# InkTime_Schematic.net
KiCad netlist of a schematic drawn in EAGLE
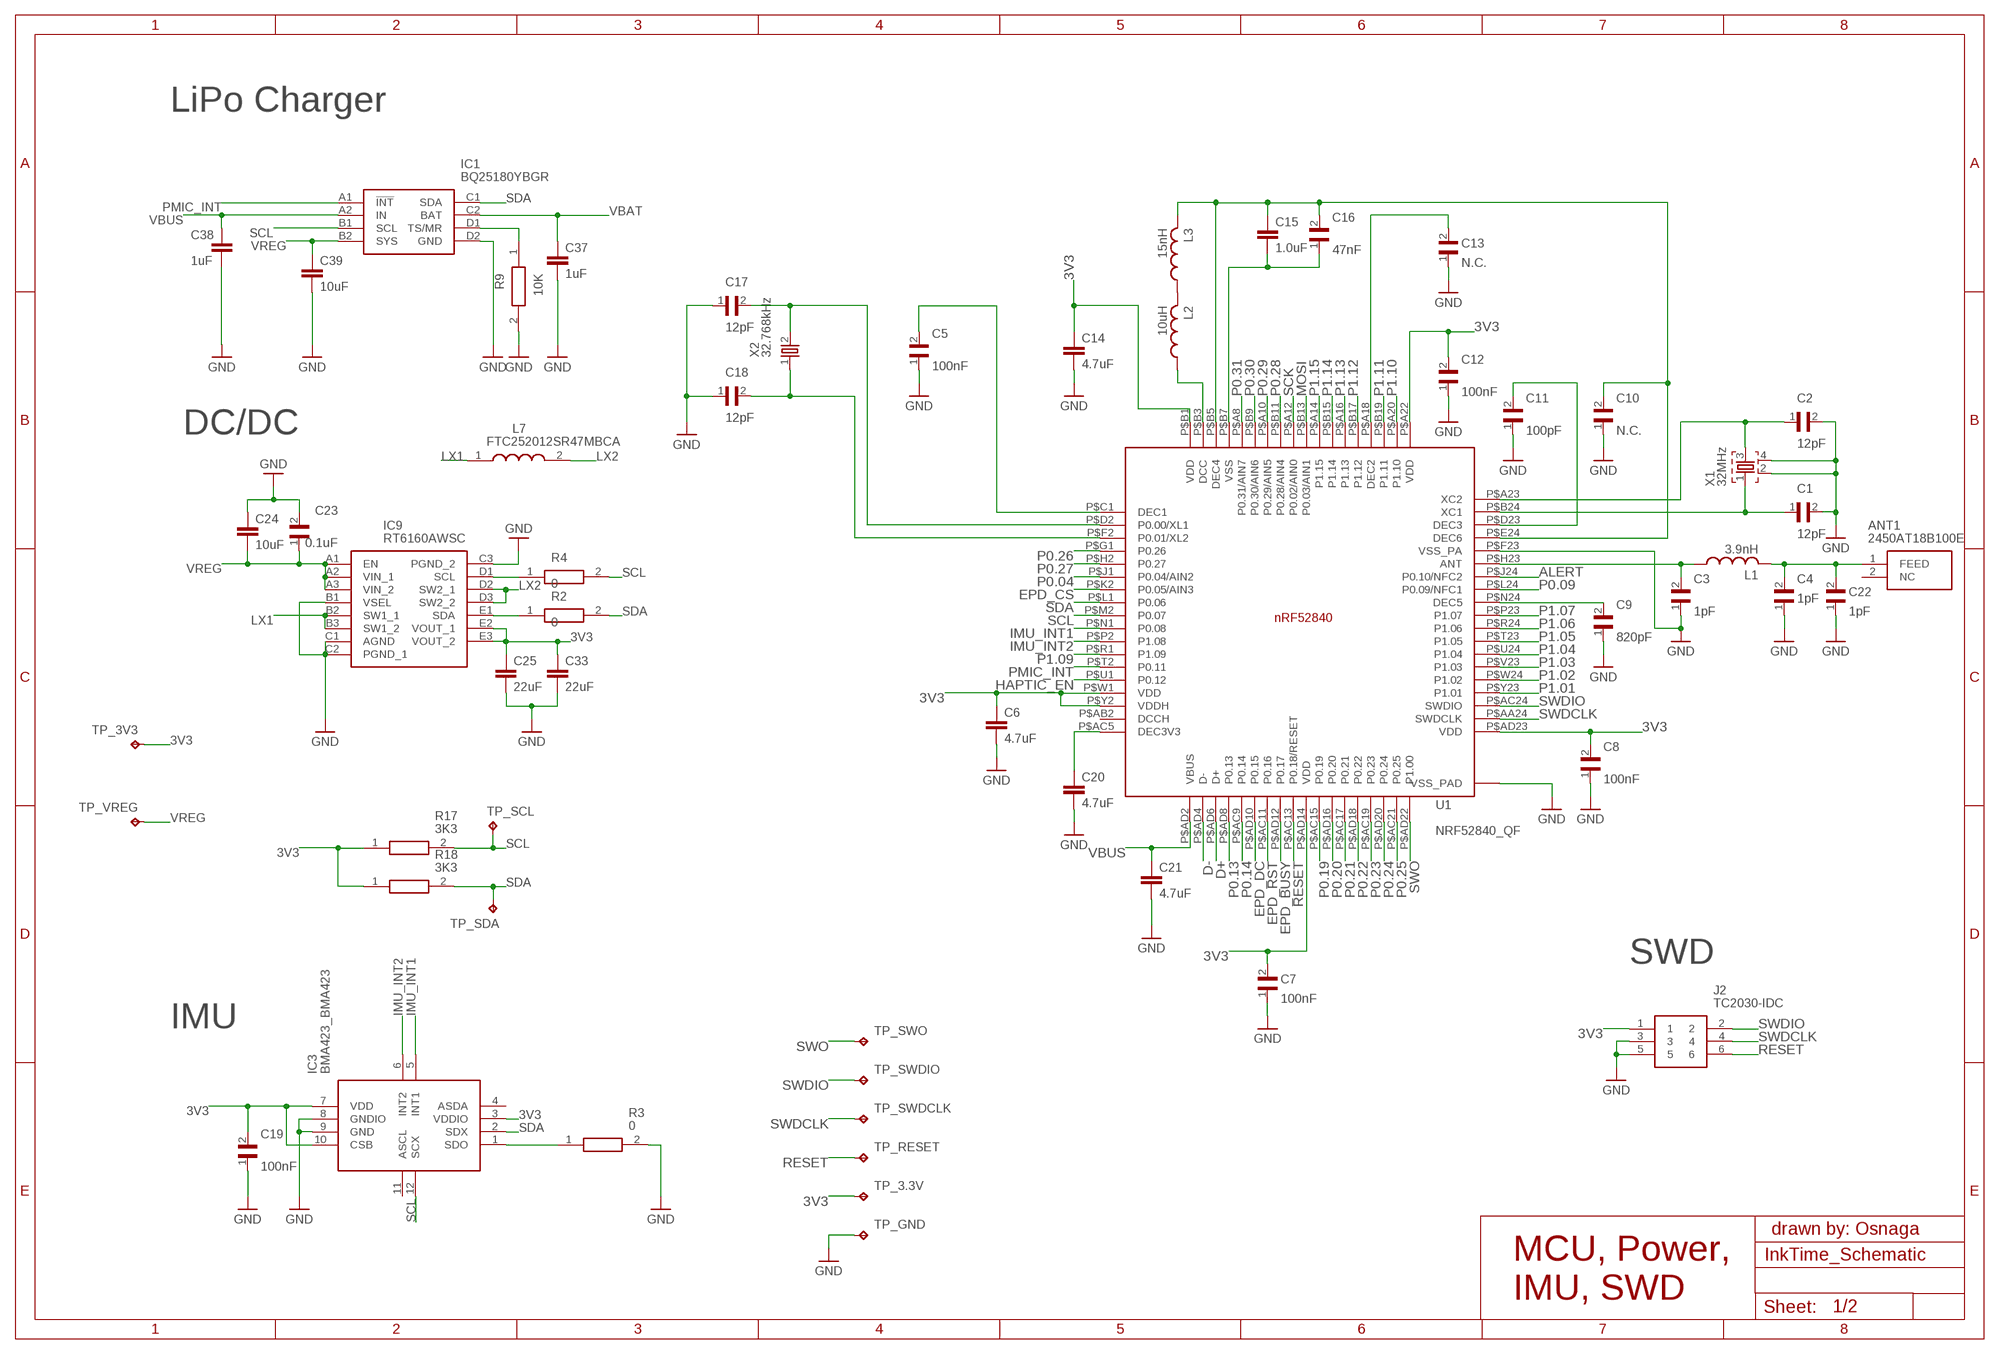
[diagram p0: schematic, sheet 1]
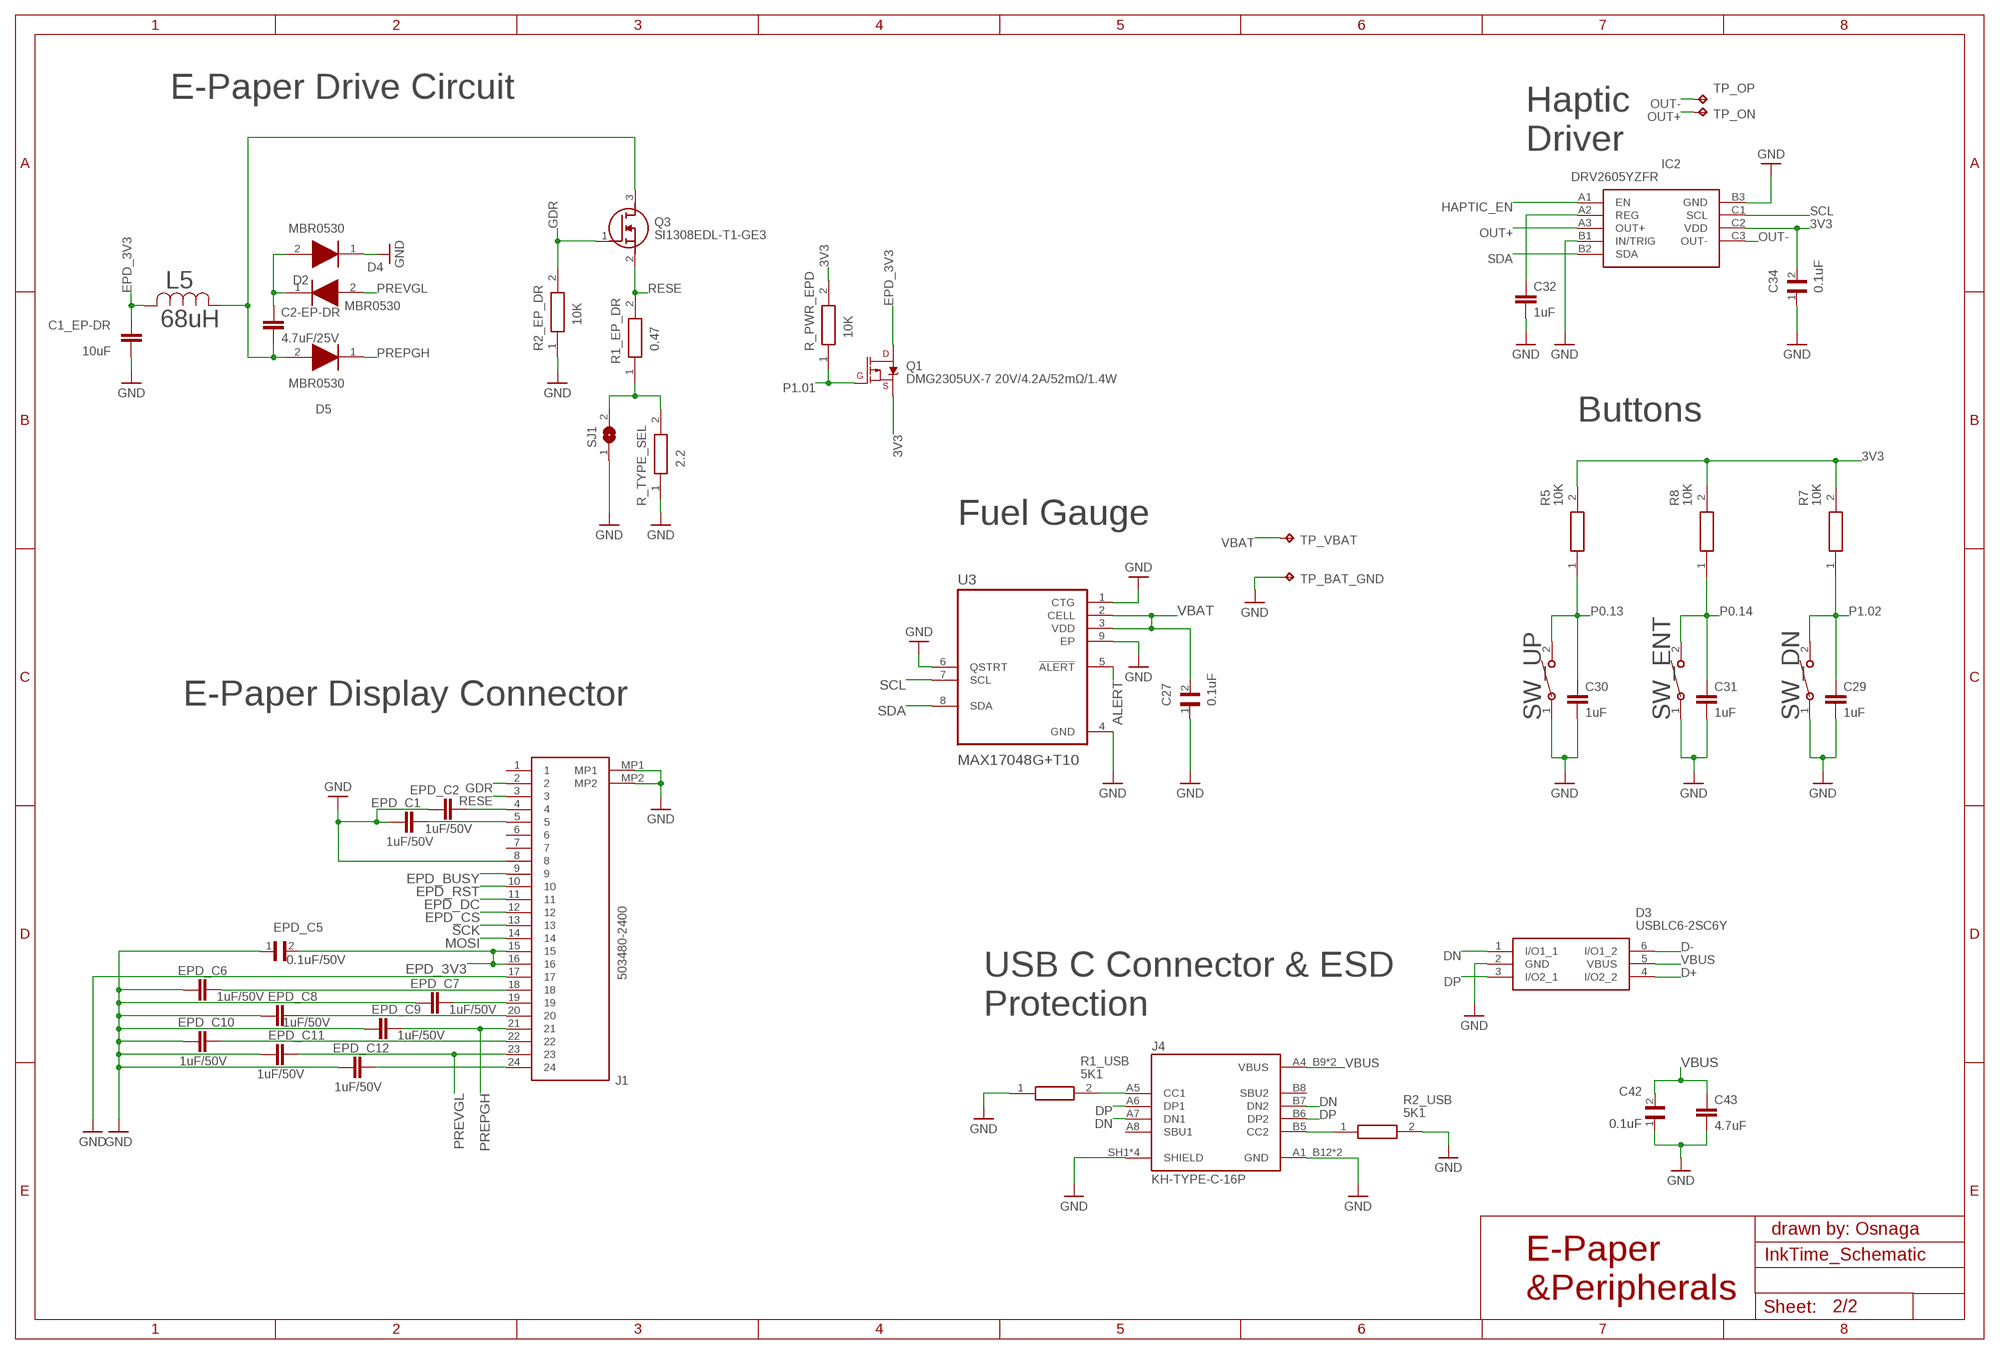
[diagram p1: schematic, sheet 2]

(export (version "E")
  (design (tool "Eeschema 10.0.6"))
  (components
    (comp (ref "C1_EP-DR")
      (value "10uF")
      (footprint "eagle-import:PERFECT_0402_0402")
      (libsource (lib "eagle-import") (part "PERFECT_0402_CAP_0402"))
    )
    (comp (ref "C2-EP-DR")
      (value "4.7uF/25V")
      (footprint "eagle-import:PERFECT_0402_0402")
      (libsource (lib "eagle-import") (part "PERFECT_0402_CAP_0402"))
    )
    (comp (ref "C27")
      (value "0.1uF")
      (footprint "eagle-import:GRM011R60J152KE01L_2_CAPC0201X13N")
      (fields (field (name "MF") "Murata") (field (name "MP") "GRM011R60J152KE01L"))
      (libsource (lib "eagle-import") (part "GRM011R60J152KE01L_2_GRM011R60J152KE01L"))
    )
    (comp (ref "C29")
      (value "1uF")
      (footprint "eagle-import:PERFECT_0402_0402")
      (libsource (lib "eagle-import") (part "PERFECT_0402_CAP_0402"))
    )
    (comp (ref "C30")
      (value "1uF")
      (footprint "eagle-import:PERFECT_0402_0402")
      (libsource (lib "eagle-import") (part "PERFECT_0402_CAP_0402"))
    )
    (comp (ref "C31")
      (value "1uF")
      (footprint "eagle-import:PERFECT_0402_0402")
      (libsource (lib "eagle-import") (part "PERFECT_0402_CAP_0402"))
    )
    (comp (ref "C32")
      (value "1uF")
      (footprint "eagle-import:PERFECT_0402_0402")
      (libsource (lib "eagle-import") (part "PERFECT_0402_CAP_0402"))
    )
    (comp (ref "C34")
      (value "0.1uF")
      (footprint "eagle-import:GRM011R60J152KE01L_2_CAPC0201X13N")
      (fields (field (name "MF") "Murata") (field (name "MP") "GRM011R60J152KE01L"))
      (libsource (lib "eagle-import") (part "GRM011R60J152KE01L_2_GRM011R60J152KE01L"))
    )
    (comp (ref "C42")
      (value "0.1uF")
      (footprint "eagle-import:GRM011R60J152KE01L_2_CAPC0201X13N")
      (fields (field (name "MF") "Murata") (field (name "MP") "GRM011R60J152KE01L"))
      (libsource (lib "eagle-import") (part "GRM011R60J152KE01L_2_GRM011R60J152KE01L"))
    )
    (comp (ref "C43")
      (value "4.7uF")
      (footprint "eagle-import:PERFECT_0402_0402")
      (libsource (lib "eagle-import") (part "PERFECT_0402_CAP_0402"))
    )
    (comp (ref "D2")
      (value "MBR0530")
      (footprint "eagle-import:ESP32_C6_LIBRARY_5_SOD3716X135N")
      (fields (field (name "MF") "ON Semiconductor"))
      (libsource (lib "eagle-import") (part "ESP32_C6_LIBRARY_5_MBR0530"))
    )
    (comp (ref "D3")
      (value "USBLC6-2SC6Y")
      (footprint "eagle-import:ESP32_C6_LIBRARY_3_SOT95P280X145-6N")
      (fields (field (name "MF") "STMicroelectronics"))
      (libsource (lib "eagle-import") (part "ESP32_C6_LIBRARY_3_USBLC6-2SC6Y"))
    )
    (comp (ref "D4")
      (value "MBR0530")
      (footprint "eagle-import:ESP32_C6_LIBRARY_5_SOD3716X135N")
      (fields (field (name "MF") "ON Semiconductor"))
      (libsource (lib "eagle-import") (part "ESP32_C6_LIBRARY_5_MBR0530"))
    )
    (comp (ref "D5")
      (value "MBR0530")
      (footprint "eagle-import:ESP32_C6_LIBRARY_5_SOD3716X135N")
      (fields (field (name "MF") "ON Semiconductor"))
      (libsource (lib "eagle-import") (part "ESP32_C6_LIBRARY_5_MBR0530"))
    )
    (comp (ref "EPD_C1")
      (value "1uF/50V")
      (footprint "eagle-import:PERFECT_0402_0402")
      (libsource (lib "eagle-import") (part "PERFECT_0402_CAP_0402"))
    )
    (comp (ref "EPD_C2")
      (value "1uF/50V")
      (footprint "eagle-import:PERFECT_0402_0402")
      (libsource (lib "eagle-import") (part "PERFECT_0402_CAP_0402"))
    )
    (comp (ref "EPD_C5")
      (value "0.1uF/50V")
      (footprint "eagle-import:GRM011R60J152KE01L_2_CAPC0201X13N")
      (fields (field (name "MF") "Murata") (field (name "MP") "GRM011R60J152KE01L"))
      (libsource (lib "eagle-import") (part "GRM011R60J152KE01L_2_GRM011R60J152KE01L"))
    )
    (comp (ref "EPD_C6")
      (value "1uF/50V")
      (footprint "eagle-import:PERFECT_0402_0402")
      (libsource (lib "eagle-import") (part "PERFECT_0402_CAP_0402"))
    )
    (comp (ref "EPD_C7")
      (value "1uF/50V")
      (footprint "eagle-import:PERFECT_0402_0402")
      (libsource (lib "eagle-import") (part "PERFECT_0402_CAP_0402"))
    )
    (comp (ref "EPD_C8")
      (value "1uF/50V")
      (footprint "eagle-import:PERFECT_0402_0402")
      (libsource (lib "eagle-import") (part "PERFECT_0402_CAP_0402"))
    )
    (comp (ref "EPD_C9")
      (value "1uF/50V")
      (footprint "eagle-import:PERFECT_0402_0402")
      (libsource (lib "eagle-import") (part "PERFECT_0402_CAP_0402"))
    )
    (comp (ref "EPD_C10")
      (value "1uF/50V")
      (footprint "eagle-import:PERFECT_0402_0402")
      (libsource (lib "eagle-import") (part "PERFECT_0402_CAP_0402"))
    )
    (comp (ref "EPD_C11")
      (value "1uF/50V")
      (footprint "eagle-import:PERFECT_0402_0402")
      (libsource (lib "eagle-import") (part "PERFECT_0402_CAP_0402"))
    )
    (comp (ref "EPD_C12")
      (value "1uF/50V")
      (footprint "eagle-import:PERFECT_0402_0402")
      (libsource (lib "eagle-import") (part "PERFECT_0402_CAP_0402"))
    )
    (comp (ref "IC2")
      (value "DRV2605YZFR")
      (footprint "eagle-import:DRV2605YZFR_BGA9C50P3X3_144X144X62")
      (libsource (lib "eagle-import") (part "DRV2605YZFR_DRV2605YZFR"))
    )
    (comp (ref "J1")
      (value "503480-2400")
      (footprint "eagle-import:503480-2400_5034802400")
      (fields (field (name "MOUSER_PART_NUMBER") "538-503480-2400"))
      (libsource (lib "eagle-import") (part "503480-2400_503480-2400"))
    )
    (comp (ref "J4")
      (value "KH-TYPE-C-16P")
      (footprint "eagle-import:KH-TYPE-C-16P_KINGHELM_KH-TYPE-C-16P")
      (fields (field (name "MF") "kinghelm"))
      (libsource (lib "eagle-import") (part "KH-TYPE-C-16P_KH-TYPE-C-16P"))
    )
    (comp (ref "L5")
      (value "68uH")
      (footprint "eagle-import:ESP32_C6_LIBRARY_2_IND_4828-WE-TPC_WRE")
      (fields
        (field (name "MANUFACTURER_PART_NUMBER") "744043680")
        (field (name "COPYRIGHT") "Copyright (C) 2024 Ultra Librarian. All rights reserved.")
      )
      (libsource (lib "eagle-import") (part "ESP32_C6_LIBRARY_2_744043680IND_4828-WE-TPC_WRE"))
    )
    (comp (ref "Q1")
      (value "DMG2305UX-7 20V/4.2A/52mΩ/1.4W")
      (footprint "eagle-import:ESP32_C6_LIBRARY_4_ESP32_C6_LIBRARY_4_ESP32_C6_LIBRARY_4_ESP32_C6_LIBRARY_4_ESP32_WROVER_SPARKFUN-DISCRETESEMI_SOT23-3")
      (libsource (lib "eagle-import") (part "ESP32_C6_LIBRARY_4_ESP32_WROVER_SPARKFUN-DISCRETESEMI_MOSFET_PCH-DMG2305UX-7"))
    )
    (comp (ref "Q3")
      (value "SI1308EDL-T1-GE3")
      (footprint "eagle-import:ESP32_C6_LIBRARY_6_SOT65P210X110-3N")
      (fields (field (name "MF") "Vishay Siliconix"))
      (libsource (lib "eagle-import") (part "ESP32_C6_LIBRARY_6_SI1308EDL-T1-GE3"))
    )
    (comp (ref "R1_EP_DR")
      (value "0.47")
      (footprint "eagle-import:CPF0201D7K68C1_0201")
      (libsource (lib "eagle-import") (part "CPF0201D7K68C1_CPF0201D7K68C1"))
    )
    (comp (ref "R1_USB")
      (value "5K1")
      (footprint "eagle-import:CPF0201D7K68C1_0201")
      (libsource (lib "eagle-import") (part "CPF0201D7K68C1_CPF0201D7K68C1"))
    )
    (comp (ref "R2_EP_DR")
      (value "10K")
      (footprint "eagle-import:CPF0201D7K68C1_0201")
      (libsource (lib "eagle-import") (part "CPF0201D7K68C1_CPF0201D7K68C1"))
    )
    (comp (ref "R2_USB")
      (value "5K1")
      (footprint "eagle-import:CPF0201D7K68C1_0201")
      (libsource (lib "eagle-import") (part "CPF0201D7K68C1_CPF0201D7K68C1"))
    )
    (comp (ref "R5")
      (value "10K")
      (footprint "eagle-import:CPF0201D7K68C1_0201")
      (libsource (lib "eagle-import") (part "CPF0201D7K68C1_CPF0201D7K68C1"))
    )
    (comp (ref "R7")
      (value "10K")
      (footprint "eagle-import:CPF0201D7K68C1_0201")
      (libsource (lib "eagle-import") (part "CPF0201D7K68C1_CPF0201D7K68C1"))
    )
    (comp (ref "R8")
      (value "10K")
      (footprint "eagle-import:CPF0201D7K68C1_0201")
      (libsource (lib "eagle-import") (part "CPF0201D7K68C1_CPF0201D7K68C1"))
    )
    (comp (ref "R_PWR_EPD")
      (value "10K")
      (footprint "eagle-import:CPF0201D7K68C1_0201")
      (libsource (lib "eagle-import") (part "CPF0201D7K68C1_CPF0201D7K68C1"))
    )
    (comp (ref "R_TYPE_SEL")
      (value "2.2")
      (footprint "eagle-import:CPF0201D7K68C1_0201")
      (libsource (lib "eagle-import") (part "CPF0201D7K68C1_CPF0201D7K68C1"))
    )
    (comp (ref "SJ1")
      (value "ESP32_C6_LIBRARY_7_JUMPER_SJ")
      (footprint "eagle-import:ESP32_C6_LIBRARY_7_JUMPER_SJ")
      (libsource (lib "eagle-import") (part "ESP32_C6_LIBRARY_7_JUMPER_SJ"))
    )
    (comp (ref "SW_DN")
      (value "2025-10-22_07-23-44_LIBRARY_EVP-AKE31ASW_EVP-AKE31A_PAN")
      (footprint "eagle-import:2025-10-22_07-23-44_LIBRARY_SW_EVP-AKE31A_PAN")
      (fields
        (field (name "MANUFACTURER_PART_NUMBER") "EVP-AKE31A")
        (field (name "COPYRIGHT") "Copyright (C) 2025 Ultra Librarian. All rights reserved.")
      )
      (libsource (lib "eagle-import") (part "2025-10-22_07-23-44_LIBRARY_EVP-AKE31ASW_EVP-AKE31A_PAN"))
    )
    (comp (ref "SW_ENT")
      (value "2025-10-22_07-23-44_LIBRARY_EVP-AKE31ASW_EVP-AKE31A_PAN")
      (footprint "eagle-import:2025-10-22_07-23-44_LIBRARY_SW_EVP-AKE31A_PAN")
      (fields
        (field (name "MANUFACTURER_PART_NUMBER") "EVP-AKE31A")
        (field (name "COPYRIGHT") "Copyright (C) 2025 Ultra Librarian. All rights reserved.")
      )
      (libsource (lib "eagle-import") (part "2025-10-22_07-23-44_LIBRARY_EVP-AKE31ASW_EVP-AKE31A_PAN"))
    )
    (comp (ref "SW_UP")
      (value "2025-10-22_07-23-44_LIBRARY_EVP-AKE31ASW_EVP-AKE31A_PAN")
      (footprint "eagle-import:2025-10-22_07-23-44_LIBRARY_SW_EVP-AKE31A_PAN")
      (fields
        (field (name "MANUFACTURER_PART_NUMBER") "EVP-AKE31A")
        (field (name "COPYRIGHT") "Copyright (C) 2025 Ultra Librarian. All rights reserved.")
      )
      (libsource (lib "eagle-import") (part "2025-10-22_07-23-44_LIBRARY_EVP-AKE31ASW_EVP-AKE31A_PAN"))
    )
    (comp (ref "TP_BAT_GND")
      (value "HECTOR_WATCH_1_TPTP20R")
      (footprint "eagle-import:HECTOR_WATCH_1_TP20R")
      (libsource (lib "eagle-import") (part "HECTOR_WATCH_1_TPTP20R"))
    )
    (comp (ref "TP_ON")
      (value "HECTOR_WATCH_1_TPTP20R")
      (footprint "eagle-import:HECTOR_WATCH_1_TP20R")
      (libsource (lib "eagle-import") (part "HECTOR_WATCH_1_TPTP20R"))
    )
    (comp (ref "TP_OP")
      (value "HECTOR_WATCH_1_TPTP20R")
      (footprint "eagle-import:HECTOR_WATCH_1_TP20R")
      (libsource (lib "eagle-import") (part "HECTOR_WATCH_1_TPTP20R"))
    )
    (comp (ref "TP_VBAT")
      (value "HECTOR_WATCH_1_TPTP20R")
      (footprint "eagle-import:HECTOR_WATCH_1_TP20R")
      (libsource (lib "eagle-import") (part "HECTOR_WATCH_1_TPTP20R"))
    )
    (comp (ref "U3")
      (value "MAX17048G+T10")
      (footprint "eagle-import:ESP32_C6_LIBRARY_SON50P200X200X80-9N")
      (fields (field (name "MF") "Analog Devices"))
      (libsource (lib "eagle-import") (part "ESP32_C6_LIBRARY_MAX17048G+T10"))
    )
    (comp (ref "ANT1")
      (value "2450AT18B100E")
      (footprint "eagle-import:2450AT18B100E_ANTC3216X140N")
      (fields (field (name "MOUSER_PART_NUMBER") "609-2450AT18B100E"))
      (libsource (lib "eagle-import") (part "2450AT18B100E_2450AT18B100E"))
    )
    (comp (ref "C1")
      (value "12pF")
      (footprint "eagle-import:GRM011R60J152KE01L_2_CAPC0201X13N")
      (fields (field (name "MF") "Murata") (field (name "MP") "GRM011R60J152KE01L"))
      (libsource (lib "eagle-import") (part "GRM011R60J152KE01L_2_GRM011R60J152KE01L"))
    )
    (comp (ref "C2")
      (value "12pF")
      (footprint "eagle-import:GRM011R60J152KE01L_2_CAPC0201X13N")
      (fields (field (name "MF") "Murata") (field (name "MP") "GRM011R60J152KE01L"))
      (libsource (lib "eagle-import") (part "GRM011R60J152KE01L_2_GRM011R60J152KE01L"))
    )
    (comp (ref "C3")
      (value "1pF")
      (footprint "eagle-import:GRM011R60J152KE01L_2_CAPC0201X13N")
      (fields (field (name "MF") "Murata") (field (name "MP") "GRM011R60J152KE01L"))
      (libsource (lib "eagle-import") (part "GRM011R60J152KE01L_2_GRM011R60J152KE01L"))
    )
    (comp (ref "C4")
      (value "1pF")
      (footprint "eagle-import:GRM011R60J152KE01L_2_CAPC0201X13N")
      (fields (field (name "MF") "Murata") (field (name "MP") "GRM011R60J152KE01L"))
      (libsource (lib "eagle-import") (part "GRM011R60J152KE01L_2_GRM011R60J152KE01L"))
    )
    (comp (ref "C5")
      (value "100nF")
      (footprint "eagle-import:GRM011R60J152KE01L_2_CAPC0201X13N")
      (fields (field (name "MF") "Murata") (field (name "MP") "GRM011R60J152KE01L"))
      (libsource (lib "eagle-import") (part "GRM011R60J152KE01L_2_GRM011R60J152KE01L"))
    )
    (comp (ref "C6")
      (value "4.7uF")
      (footprint "eagle-import:PERFECT_0402_0402")
      (libsource (lib "eagle-import") (part "PERFECT_0402_CAP_0402"))
    )
    (comp (ref "C7")
      (value "100nF")
      (footprint "eagle-import:GRM011R60J152KE01L_2_CAPC0201X13N")
      (fields (field (name "MF") "Murata") (field (name "MP") "GRM011R60J152KE01L"))
      (libsource (lib "eagle-import") (part "GRM011R60J152KE01L_2_GRM011R60J152KE01L"))
    )
    (comp (ref "C8")
      (value "100nF")
      (footprint "eagle-import:GRM011R60J152KE01L_2_CAPC0201X13N")
      (fields (field (name "MF") "Murata") (field (name "MP") "GRM011R60J152KE01L"))
      (libsource (lib "eagle-import") (part "GRM011R60J152KE01L_2_GRM011R60J152KE01L"))
    )
    (comp (ref "C9")
      (value "820pF")
      (footprint "eagle-import:GRM011R60J152KE01L_2_CAPC0201X13N")
      (fields (field (name "MF") "Murata") (field (name "MP") "GRM011R60J152KE01L"))
      (libsource (lib "eagle-import") (part "GRM011R60J152KE01L_2_GRM011R60J152KE01L"))
    )
    (comp (ref "C10")
      (value "N.C.")
      (footprint "eagle-import:GRM011R60J152KE01L_2_CAPC0201X13N")
      (fields (field (name "MF") "Murata") (field (name "MP") "GRM011R60J152KE01L"))
      (libsource (lib "eagle-import") (part "GRM011R60J152KE01L_2_GRM011R60J152KE01L"))
    )
    (comp (ref "C11")
      (value "100pF")
      (footprint "eagle-import:GRM011R60J152KE01L_2_CAPC0201X13N")
      (fields (field (name "MF") "Murata") (field (name "MP") "GRM011R60J152KE01L"))
      (libsource (lib "eagle-import") (part "GRM011R60J152KE01L_2_GRM011R60J152KE01L"))
    )
    (comp (ref "C12")
      (value "100nF")
      (footprint "eagle-import:GRM011R60J152KE01L_2_CAPC0201X13N")
      (fields (field (name "MF") "Murata") (field (name "MP") "GRM011R60J152KE01L"))
      (libsource (lib "eagle-import") (part "GRM011R60J152KE01L_2_GRM011R60J152KE01L"))
    )
    (comp (ref "C13")
      (value "N.C.")
      (footprint "eagle-import:GRM011R60J152KE01L_2_CAPC0201X13N")
      (fields (field (name "MF") "Murata") (field (name "MP") "GRM011R60J152KE01L"))
      (libsource (lib "eagle-import") (part "GRM011R60J152KE01L_2_GRM011R60J152KE01L"))
    )
    (comp (ref "C14")
      (value "4.7uF")
      (footprint "eagle-import:PERFECT_0402_0402")
      (libsource (lib "eagle-import") (part "PERFECT_0402_CAP_0402"))
    )
    (comp (ref "C15")
      (value "1.0uF")
      (footprint "eagle-import:PERFECT_0402_0402")
      (libsource (lib "eagle-import") (part "PERFECT_0402_CAP_0402"))
    )
    (comp (ref "C16")
      (value "47nF")
      (footprint "eagle-import:GRM011R60J152KE01L_2_CAPC0201X13N")
      (fields (field (name "MF") "Murata") (field (name "MP") "GRM011R60J152KE01L"))
      (libsource (lib "eagle-import") (part "GRM011R60J152KE01L_2_GRM011R60J152KE01L"))
    )
    (comp (ref "C17")
      (value "12pF")
      (footprint "eagle-import:GRM011R60J152KE01L_2_CAPC0201X13N")
      (fields (field (name "MF") "Murata") (field (name "MP") "GRM011R60J152KE01L"))
      (libsource (lib "eagle-import") (part "GRM011R60J152KE01L_2_GRM011R60J152KE01L"))
    )
    (comp (ref "C18")
      (value "12pF")
      (footprint "eagle-import:GRM011R60J152KE01L_2_CAPC0201X13N")
      (fields (field (name "MF") "Murata") (field (name "MP") "GRM011R60J152KE01L"))
      (libsource (lib "eagle-import") (part "GRM011R60J152KE01L_2_GRM011R60J152KE01L"))
    )
    (comp (ref "C19")
      (value "100nF")
      (footprint "eagle-import:GRM011R60J152KE01L_2_CAPC0201X13N")
      (fields (field (name "MF") "Murata") (field (name "MP") "GRM011R60J152KE01L"))
      (libsource (lib "eagle-import") (part "GRM011R60J152KE01L_2_GRM011R60J152KE01L"))
    )
    (comp (ref "C20")
      (value "4.7uF")
      (footprint "eagle-import:PERFECT_0402_0402")
      (libsource (lib "eagle-import") (part "PERFECT_0402_CAP_0402"))
    )
    (comp (ref "C21")
      (value "4.7uF")
      (footprint "eagle-import:PERFECT_0402_0402")
      (libsource (lib "eagle-import") (part "PERFECT_0402_CAP_0402"))
    )
    (comp (ref "C22")
      (value "1pF")
      (footprint "eagle-import:GRM011R60J152KE01L_2_CAPC0201X13N")
      (fields (field (name "MF") "Murata") (field (name "MP") "GRM011R60J152KE01L"))
      (libsource (lib "eagle-import") (part "GRM011R60J152KE01L_2_GRM011R60J152KE01L"))
    )
    (comp (ref "C23")
      (value "0.1uF")
      (footprint "eagle-import:GRM011R60J152KE01L_2_CAPC0201X13N")
      (fields (field (name "MF") "Murata") (field (name "MP") "GRM011R60J152KE01L"))
      (libsource (lib "eagle-import") (part "GRM011R60J152KE01L_2_GRM011R60J152KE01L"))
    )
    (comp (ref "C24")
      (value "10uF")
      (footprint "eagle-import:PERFECT_0402_0402")
      (libsource (lib "eagle-import") (part "PERFECT_0402_CAP_0402"))
    )
    (comp (ref "C25")
      (value "22uF")
      (footprint "eagle-import:PERFECT_0402_0402")
      (libsource (lib "eagle-import") (part "PERFECT_0402_CAP_0402"))
    )
    (comp (ref "C33")
      (value "22uF")
      (footprint "eagle-import:PERFECT_0402_0402")
      (libsource (lib "eagle-import") (part "PERFECT_0402_CAP_0402"))
    )
    (comp (ref "C37")
      (value "1uF")
      (footprint "eagle-import:PERFECT_0402_0402")
      (libsource (lib "eagle-import") (part "PERFECT_0402_CAP_0402"))
    )
    (comp (ref "C38")
      (value "1uF")
      (footprint "eagle-import:PERFECT_0402_0402")
      (libsource (lib "eagle-import") (part "PERFECT_0402_CAP_0402"))
    )
    (comp (ref "C39")
      (value "10uF")
      (footprint "eagle-import:PERFECT_0402_0402")
      (libsource (lib "eagle-import") (part "PERFECT_0402_CAP_0402"))
    )
    (comp (ref "IC1")
      (value "BQ25180YBGR")
      (footprint "eagle-import:BQ25180YBGR_BGA8C40P2X4_100X155X50")
      (fields (field (name "MOUSER_PART_NUMBER") "595-BQ25180YBGR"))
      (libsource (lib "eagle-import") (part "BQ25180YBGR_BQ25180YBGR"))
    )
    (comp (ref "IC3")
      (value "BMA423_BMA423")
      (footprint "eagle-import:BMA423_BMA423")
      (fields (field (name "ARROW_PART_NUMBER") "BMA423") (field (name "MOUSER_PART_NUMBER") "262-BMA423"))
      (libsource (lib "eagle-import") (part "BMA423_BMA423"))
    )
    (comp (ref "IC9")
      (value "RT6160AWSC")
      (footprint "eagle-import:RT6160AWSC_BGA15C40P3X5_140X230X60")
      (fields (field (name "MOUSER_PART_NUMBER") "835-RT6160AWSC"))
      (libsource (lib "eagle-import") (part "RT6160AWSC_RT6160AWSC"))
    )
    (comp (ref "J2")
      (value "TC2030-IDC")
      (footprint "eagle-import:TC2030-IDC_TC2030IDC")
      (libsource (lib "eagle-import") (part "TC2030-IDC_TC2030-IDC"))
    )
    (comp (ref "L1")
      (value "3.9nH")
      (footprint "eagle-import:NORDIC_NRF_2_RESC0201_L")
      (libsource (lib "eagle-import") (part "NORDIC_NRF_2_INDUCTOR_0201_L"))
    )
    (comp (ref "L2")
      (value "10uH")
      (footprint "eagle-import:NORDIC_NRF_2_RESC0201_L")
      (libsource (lib "eagle-import") (part "NORDIC_NRF_2_INDUCTOR_0201_L"))
    )
    (comp (ref "L3")
      (value "15nH")
      (footprint "eagle-import:NORDIC_NRF_2_RESC0201_L")
      (libsource (lib "eagle-import") (part "NORDIC_NRF_2_INDUCTOR_0201_L"))
    )
    (comp (ref "L7")
      (value "FTC252012SR47MBCA")
      (footprint "eagle-import:MLP2016SR47MT0S1_INDC2016X100N")
      (libsource (lib "eagle-import") (part "MLP2016SR47MT0S1_FTC252012SR47MBCA"))
    )
    (comp (ref "R2")
      (value "0")
      (footprint "eagle-import:CPF0201D7K68C1_0201")
      (libsource (lib "eagle-import") (part "CPF0201D7K68C1_CPF0201D7K68C1"))
    )
    (comp (ref "R3")
      (value "0")
      (footprint "eagle-import:CPF0201D7K68C1_0201")
      (libsource (lib "eagle-import") (part "CPF0201D7K68C1_CPF0201D7K68C1"))
    )
    (comp (ref "R4")
      (value "0")
      (footprint "eagle-import:CPF0201D7K68C1_0201")
      (libsource (lib "eagle-import") (part "CPF0201D7K68C1_CPF0201D7K68C1"))
    )
    (comp (ref "R9")
      (value "10K")
      (footprint "eagle-import:CPF0201D7K68C1_0201")
      (libsource (lib "eagle-import") (part "CPF0201D7K68C1_CPF0201D7K68C1"))
    )
    (comp (ref "R17")
      (value "3K3")
      (footprint "eagle-import:CPF0201D7K68C1_0201")
      (libsource (lib "eagle-import") (part "CPF0201D7K68C1_CPF0201D7K68C1"))
    )
    (comp (ref "R18")
      (value "3K3")
      (footprint "eagle-import:CPF0201D7K68C1_0201")
      (libsource (lib "eagle-import") (part "CPF0201D7K68C1_CPF0201D7K68C1"))
    )
    (comp (ref "TP_3.3V")
      (value "HECTOR_WATCH_1_TPTP20R")
      (footprint "eagle-import:HECTOR_WATCH_1_TP20R")
      (libsource (lib "eagle-import") (part "HECTOR_WATCH_1_TPTP20R"))
    )
    (comp (ref "TP_3V3")
      (value "HECTOR_WATCH_1_TPTP20R")
      (footprint "eagle-import:HECTOR_WATCH_1_TP20R")
      (libsource (lib "eagle-import") (part "HECTOR_WATCH_1_TPTP20R"))
    )
    (comp (ref "TP_GND")
      (value "HECTOR_WATCH_1_TPTP20R")
      (footprint "eagle-import:HECTOR_WATCH_1_TP20R")
      (libsource (lib "eagle-import") (part "HECTOR_WATCH_1_TPTP20R"))
    )
    (comp (ref "TP_RESET")
      (value "HECTOR_WATCH_1_TPTP20R")
      (footprint "eagle-import:HECTOR_WATCH_1_TP20R")
      (libsource (lib "eagle-import") (part "HECTOR_WATCH_1_TPTP20R"))
    )
    (comp (ref "TP_SCL")
      (value "HECTOR_WATCH_1_TPTP20R")
      (footprint "eagle-import:HECTOR_WATCH_1_TP20R")
      (libsource (lib "eagle-import") (part "HECTOR_WATCH_1_TPTP20R"))
    )
    (comp (ref "TP_SDA")
      (value "HECTOR_WATCH_1_TPTP20R")
      (footprint "eagle-import:HECTOR_WATCH_1_TP20R")
      (libsource (lib "eagle-import") (part "HECTOR_WATCH_1_TPTP20R"))
    )
    (comp (ref "TP_SWDCLK")
      (value "HECTOR_WATCH_1_TPTP20R")
      (footprint "eagle-import:HECTOR_WATCH_1_TP20R")
      (libsource (lib "eagle-import") (part "HECTOR_WATCH_1_TPTP20R"))
    )
    (comp (ref "TP_SWDIO")
      (value "HECTOR_WATCH_1_TPTP20R")
      (footprint "eagle-import:HECTOR_WATCH_1_TP20R")
      (libsource (lib "eagle-import") (part "HECTOR_WATCH_1_TPTP20R"))
    )
    (comp (ref "TP_SWO")
      (value "HECTOR_WATCH_1_TPTP20R")
      (footprint "eagle-import:HECTOR_WATCH_1_TP20R")
      (libsource (lib "eagle-import") (part "HECTOR_WATCH_1_TPTP20R"))
    )
    (comp (ref "TP_VREG")
      (value "HECTOR_WATCH_1_TPTP20R")
      (footprint "eagle-import:HECTOR_WATCH_1_TP20R")
      (libsource (lib "eagle-import") (part "HECTOR_WATCH_1_TPTP20R"))
    )
    (comp (ref "U1")
      (value "NRF52840_QF")
      (footprint "eagle-import:NORDIC_NRF_4_AQFN50P700X700X85_HS-74N")
      (libsource (lib "eagle-import") (part "NORDIC_NRF_4_NRF52840_QF"))
    )
    (comp (ref "X1")
      (value "32MHz")
      (footprint "eagle-import:NORDIC_NRF_BT-XTAL_2016_N")
      (libsource (lib "eagle-import") (part "NORDIC_NRF_XTAL_32MHZ"))
    )
    (comp (ref "X2")
      (value "32.768kHz")
      (footprint "eagle-import:NORDIC_NRF_1_XTAL_3215_N")
      (libsource (lib "eagle-import") (part "NORDIC_NRF_1_XTAL_32KHZ"))
    )
  )
  (nets
    (net (code "1") (name "3V3") (class "Default")
      (node (ref "C12") (pin "2") (pinfunction "2_2") (pintype "passive"))
      (node (ref "C14") (pin "1") (pinfunction "1_1") (pintype "passive"))
      (node (ref "C19") (pin "2") (pinfunction "2_2") (pintype "passive"))
      (node (ref "C25") (pin "1") (pinfunction "1_1") (pintype "passive"))
      (node (ref "C33") (pin "1") (pinfunction "1_1") (pintype "passive"))
      (node (ref "C34") (pin "2") (pinfunction "2_2") (pintype "passive"))
      (node (ref "C6") (pin "1") (pinfunction "1_1") (pintype "passive"))
      (node (ref "C7") (pin "2") (pinfunction "2_2") (pintype "passive"))
      (node (ref "C8") (pin "2") (pinfunction "2_2") (pintype "passive"))
      (node (ref "IC2") (pin "C2") (pinfunction "VDD_C2") (pintype "bidirectional"))
      (node (ref "IC3") (pin "10") (pinfunction "CSB_10") (pintype "bidirectional"))
      (node (ref "IC3") (pin "3") (pinfunction "VDDIO_3") (pintype "bidirectional"))
      (node (ref "IC3") (pin "7") (pinfunction "VDD_7") (pintype "bidirectional"))
      (node (ref "IC9") (pin "E2") (pinfunction "VOUT_1_E2") (pintype "bidirectional"))
      (node (ref "IC9") (pin "E3") (pinfunction "VOUT_2_E3") (pintype "bidirectional"))
      (node (ref "J2") (pin "1") (pinfunction "1_1") (pintype "bidirectional"))
      (node (ref "Q1") (pin "2") (pinfunction "S_2") (pintype "bidirectional"))
      (node (ref "R17") (pin "1") (pinfunction "1_1") (pintype "bidirectional"))
      (node (ref "R18") (pin "1") (pinfunction "1_1") (pintype "bidirectional"))
      (node (ref "R5") (pin "2") (pinfunction "2_2") (pintype "bidirectional"))
      (node (ref "R7") (pin "2") (pinfunction "2_2") (pintype "bidirectional"))
      (node (ref "R8") (pin "2") (pinfunction "2_2") (pintype "bidirectional"))
      (node (ref "R_PWR_EPD") (pin "2") (pinfunction "2_2") (pintype "bidirectional"))
      (node (ref "TP_3.3V") (pin "TP") (pinfunction "TP_TP") (pintype "input"))
      (node (ref "TP_3V3") (pin "TP") (pinfunction "TP_TP") (pintype "input"))
      (node (ref "U1") (pin "P$A22") (pinfunction "VDD_P$A22") (pintype "power_in"))
      (node (ref "U1") (pin "P$AD14") (pinfunction "VDD_P$AD14") (pintype "power_in"))
      (node (ref "U1") (pin "P$AD23") (pinfunction "VDD_P$AD23") (pintype "power_in"))
      (node (ref "U1") (pin "P$B1") (pinfunction "VDD_P$B1") (pintype "power_in"))
      (node (ref "U1") (pin "P$W1") (pinfunction "VDD_P$W1") (pintype "power_in"))
      (node (ref "U1") (pin "P$Y2") (pinfunction "VDDH_P$Y2") (pintype "power_in"))
    )
    (net (code "2") (name "ALERT") (class "Default")
      (node (ref "U1") (pin "P$J24") (pinfunction "P0.10/NFC2_P$J24") (pintype "bidirectional"))
      (node (ref "U3") (pin "5") (pinfunction "~{ALERT}_5") (pintype "output"))
    )
    (net (code "3") (name "D+") (class "Default")
      (node (ref "D3") (pin "4") (pinfunction "I/O2_2_4") (pintype "bidirectional"))
      (node (ref "U1") (pin "P$AD6") (pinfunction "D+_P$AD6") (pintype "bidirectional"))
    )
    (net (code "4") (name "D-") (class "Default")
      (node (ref "D3") (pin "6") (pinfunction "I/O1_2_6") (pintype "bidirectional"))
      (node (ref "U1") (pin "P$AD4") (pinfunction "D-_P$AD4") (pintype "bidirectional"))
    )
    (net (code "5") (name "DN") (class "Default")
      (node (ref "D3") (pin "1") (pinfunction "I/O1_1_1") (pintype "bidirectional"))
      (node (ref "J4") (pin "A7") (pinfunction "DN1_A7") (pintype "bidirectional"))
      (node (ref "J4") (pin "B7") (pinfunction "DN2_B7") (pintype "bidirectional"))
    )
    (net (code "6") (name "DP") (class "Default")
      (node (ref "D3") (pin "3") (pinfunction "I/O2_1_3") (pintype "bidirectional"))
      (node (ref "J4") (pin "A6") (pinfunction "DP1_A6") (pintype "bidirectional"))
      (node (ref "J4") (pin "B6") (pinfunction "DP2_B6") (pintype "bidirectional"))
    )
    (net (code "7") (name "EPD_3V3") (class "Default")
      (node (ref "C1_EP-DR") (pin "1") (pinfunction "1_1") (pintype "passive"))
      (node (ref "EPD_C5") (pin "2") (pinfunction "2_2") (pintype "passive"))
      (node (ref "J1") (pin "15") (pinfunction "15_15") (pintype "bidirectional"))
      (node (ref "J1") (pin "16") (pinfunction "16_16") (pintype "bidirectional"))
      (node (ref "L5") (pin "2") (pinfunction "2_2") (pintype "passive"))
      (node (ref "Q1") (pin "3") (pinfunction "D_3") (pintype "bidirectional"))
    )
    (net (code "8") (name "EPD_BUSY") (class "Default")
      (node (ref "J1") (pin "9") (pinfunction "9_9") (pintype "bidirectional"))
      (node (ref "U1") (pin "P$AD12") (pinfunction "P0.17_P$AD12") (pintype "bidirectional"))
    )
    (net (code "9") (name "EPD_CS") (class "Default")
      (node (ref "J1") (pin "12") (pinfunction "12_12") (pintype "bidirectional"))
      (node (ref "U1") (pin "P$K2") (pinfunction "P0.05/AIN3_P$K2") (pintype "bidirectional"))
    )
    (net (code "10") (name "EPD_DC") (class "Default")
      (node (ref "J1") (pin "11") (pinfunction "11_11") (pintype "bidirectional"))
      (node (ref "U1") (pin "P$AD10") (pinfunction "P0.15_P$AD10") (pintype "bidirectional"))
    )
    (net (code "11") (name "EPD_RST") (class "Default")
      (node (ref "J1") (pin "10") (pinfunction "10_10") (pintype "bidirectional"))
      (node (ref "U1") (pin "P$AC11") (pinfunction "P0.16_P$AC11") (pintype "bidirectional"))
    )
    (net (code "12") (name "GDR") (class "Default")
      (node (ref "J1") (pin "2") (pinfunction "2_2") (pintype "bidirectional"))
      (node (ref "Q3") (pin "1") (pinfunction "G_1") (pintype "bidirectional"))
      (node (ref "R2_EP_DR") (pin "2") (pinfunction "2_2") (pintype "bidirectional"))
    )
    (net (code "13") (name "GND") (class "Default")
      (node (ref "C1") (pin "2") (pinfunction "2_2") (pintype "passive"))
      (node (ref "C10") (pin "1") (pinfunction "1_1") (pintype "passive"))
      (node (ref "C11") (pin "1") (pinfunction "1_1") (pintype "passive"))
      (node (ref "C12") (pin "1") (pinfunction "1_1") (pintype "passive"))
      (node (ref "C13") (pin "1") (pinfunction "1_1") (pintype "passive"))
      (node (ref "C14") (pin "2") (pinfunction "2_2") (pintype "passive"))
      (node (ref "C17") (pin "1") (pinfunction "1_1") (pintype "passive"))
      (node (ref "C18") (pin "1") (pinfunction "1_1") (pintype "passive"))
      (node (ref "C19") (pin "1") (pinfunction "1_1") (pintype "passive"))
      (node (ref "C1_EP-DR") (pin "2") (pinfunction "2_2") (pintype "passive"))
      (node (ref "C2") (pin "2") (pinfunction "2_2") (pintype "passive"))
      (node (ref "C20") (pin "2") (pinfunction "2_2") (pintype "passive"))
      (node (ref "C21") (pin "2") (pinfunction "2_2") (pintype "passive"))
      (node (ref "C22") (pin "1") (pinfunction "1_1") (pintype "passive"))
      (node (ref "C23") (pin "2") (pinfunction "2_2") (pintype "passive"))
      (node (ref "C24") (pin "1") (pinfunction "1_1") (pintype "passive"))
      (node (ref "C25") (pin "2") (pinfunction "2_2") (pintype "passive"))
      (node (ref "C27") (pin "1") (pinfunction "1_1") (pintype "passive"))
      (node (ref "C29") (pin "2") (pinfunction "2_2") (pintype "passive"))
      (node (ref "C3") (pin "1") (pinfunction "1_1") (pintype "passive"))
      (node (ref "C30") (pin "2") (pinfunction "2_2") (pintype "passive"))
      (node (ref "C31") (pin "2") (pinfunction "2_2") (pintype "passive"))
      (node (ref "C32") (pin "2") (pinfunction "2_2") (pintype "passive"))
      (node (ref "C33") (pin "2") (pinfunction "2_2") (pintype "passive"))
      (node (ref "C34") (pin "1") (pinfunction "1_1") (pintype "passive"))
      (node (ref "C37") (pin "2") (pinfunction "2_2") (pintype "passive"))
      (node (ref "C38") (pin "2") (pinfunction "2_2") (pintype "passive"))
      (node (ref "C39") (pin "2") (pinfunction "2_2") (pintype "passive"))
      (node (ref "C4") (pin "1") (pinfunction "1_1") (pintype "passive"))
      (node (ref "C42") (pin "1") (pinfunction "1_1") (pintype "passive"))
      (node (ref "C43") (pin "2") (pinfunction "2_2") (pintype "passive"))
      (node (ref "C5") (pin "1") (pinfunction "1_1") (pintype "passive"))
      (node (ref "C6") (pin "2") (pinfunction "2_2") (pintype "passive"))
      (node (ref "C7") (pin "1") (pinfunction "1_1") (pintype "passive"))
      (node (ref "C8") (pin "1") (pinfunction "1_1") (pintype "passive"))
      (node (ref "C9") (pin "1") (pinfunction "1_1") (pintype "passive"))
      (node (ref "D3") (pin "2") (pinfunction "GND_2") (pintype "bidirectional"))
      (node (ref "D4") (pin "1") (pinfunction "K_1") (pintype "bidirectional"))
      (node (ref "EPD_C1") (pin "1") (pinfunction "1_1") (pintype "passive"))
      (node (ref "EPD_C10") (pin "1") (pinfunction "1_1") (pintype "passive"))
      (node (ref "EPD_C11") (pin "1") (pinfunction "1_1") (pintype "passive"))
      (node (ref "EPD_C12") (pin "1") (pinfunction "1_1") (pintype "passive"))
      (node (ref "EPD_C2") (pin "1") (pinfunction "1_1") (pintype "passive"))
      (node (ref "EPD_C5") (pin "1") (pinfunction "1_1") (pintype "passive"))
      (node (ref "EPD_C6") (pin "1") (pinfunction "1_1") (pintype "passive"))
      (node (ref "EPD_C7") (pin "1") (pinfunction "1_1") (pintype "passive"))
      (node (ref "EPD_C8") (pin "1") (pinfunction "1_1") (pintype "passive"))
      (node (ref "EPD_C9") (pin "1") (pinfunction "1_1") (pintype "passive"))
      (node (ref "IC1") (pin "D2") (pinfunction "GND_D2") (pintype "bidirectional"))
      (node (ref "IC2") (pin "B1") (pinfunction "IN/TRIG_B1") (pintype "bidirectional"))
      (node (ref "IC2") (pin "B3") (pinfunction "GND_B3") (pintype "bidirectional"))
      (node (ref "IC3") (pin "8") (pinfunction "GNDIO_8") (pintype "bidirectional"))
      (node (ref "IC3") (pin "9") (pinfunction "GND_9") (pintype "bidirectional"))
      (node (ref "IC9") (pin "B1") (pinfunction "VSEL_B1") (pintype "bidirectional"))
      (node (ref "IC9") (pin "C1") (pinfunction "AGND_C1") (pintype "bidirectional"))
      (node (ref "IC9") (pin "C2") (pinfunction "PGND_1_C2") (pintype "bidirectional"))
      (node (ref "IC9") (pin "C3") (pinfunction "PGND_2_C3") (pintype "bidirectional"))
      (node (ref "J1") (pin "17") (pinfunction "17_17") (pintype "bidirectional"))
      (node (ref "J1") (pin "8") (pinfunction "8_8") (pintype "bidirectional"))
      (node (ref "J1") (pin "MP1") (pinfunction "MP1_MP1") (pintype "bidirectional"))
      (node (ref "J1") (pin "MP2") (pinfunction "MP2_MP2") (pintype "bidirectional"))
      (node (ref "J2") (pin "3") (pinfunction "3_3") (pintype "bidirectional"))
      (node (ref "J2") (pin "5") (pinfunction "5_5") (pintype "bidirectional"))
      (node (ref "J4") (pin "A12_B1") (pinfunction "GND_A12_B1") (pintype "power_in"))
      (node (ref "J4") (pin "A1_B12") (pinfunction "GND_A1_B12") (pintype "power_in"))
      (node (ref "J4") (pin "SH1") (pinfunction "SHIELD_SH1") (pintype "passive"))
      (node (ref "J4") (pin "SH2") (pinfunction "SHIELD_SH2") (pintype "passive"))
      (node (ref "J4") (pin "SH3") (pinfunction "SHIELD_SH3") (pintype "passive"))
      (node (ref "J4") (pin "SH4") (pinfunction "SHIELD_SH4") (pintype "passive"))
      (node (ref "R1_USB") (pin "1") (pinfunction "1_1") (pintype "bidirectional"))
      (node (ref "R2_EP_DR") (pin "1") (pinfunction "1_1") (pintype "bidirectional"))
      (node (ref "R2_USB") (pin "2") (pinfunction "2_2") (pintype "bidirectional"))
      (node (ref "R3") (pin "2") (pinfunction "2_2") (pintype "bidirectional"))
      (node (ref "R9") (pin "2") (pinfunction "2_2") (pintype "bidirectional"))
      (node (ref "R_TYPE_SEL") (pin "1") (pinfunction "1_1") (pintype "bidirectional"))
      (node (ref "SJ1") (pin "1") (pinfunction "1_1") (pintype "passive"))
      (node (ref "SW_DN") (pin "1") (pinfunction "1_1") (pintype "passive"))
      (node (ref "SW_ENT") (pin "1") (pinfunction "1_1") (pintype "passive"))
      (node (ref "SW_UP") (pin "1") (pinfunction "1_1") (pintype "passive"))
      (node (ref "TP_BAT_GND") (pin "TP") (pinfunction "TP_TP") (pintype "input"))
      (node (ref "TP_GND") (pin "TP") (pinfunction "TP_TP") (pintype "input"))
      (node (ref "U1") (pin "P$74") (pinfunction "VSS_PAD_P$74") (pintype "bidirectional"))
      (node (ref "U1") (pin "P$75") (pinfunction "VSS_PAD_P$75") (pintype "bidirectional"))
      (node (ref "U1") (pin "P$76") (pinfunction "VSS_PAD_P$76") (pintype "bidirectional"))
      (node (ref "U1") (pin "P$77") (pinfunction "VSS_PAD_P$77") (pintype "bidirectional"))
      (node (ref "U1") (pin "P$78") (pinfunction "VSS_PAD_P$78") (pintype "bidirectional"))
      (node (ref "U1") (pin "P$79") (pinfunction "VSS_PAD_P$79") (pintype "bidirectional"))
      (node (ref "U1") (pin "P$80") (pinfunction "VSS_PAD_P$80") (pintype "bidirectional"))
      (node (ref "U1") (pin "P$81") (pinfunction "VSS_PAD_P$81") (pintype "bidirectional"))
      (node (ref "U1") (pin "P$82") (pinfunction "VSS_PAD_P$82") (pintype "bidirectional"))
      (node (ref "U1") (pin "P$83") (pinfunction "VSS_PAD_P$83") (pintype "bidirectional"))
      (node (ref "U1") (pin "P$84") (pinfunction "VSS_PAD_P$84") (pintype "bidirectional"))
      (node (ref "U1") (pin "P$85") (pinfunction "VSS_PAD_P$85") (pintype "bidirectional"))
      (node (ref "U1") (pin "P$86") (pinfunction "VSS_PAD_P$86") (pintype "bidirectional"))
      (node (ref "U1") (pin "P$87") (pinfunction "VSS_PAD_P$87") (pintype "bidirectional"))
      (node (ref "U1") (pin "P$88") (pinfunction "VSS_PAD_P$88") (pintype "bidirectional"))
      (node (ref "U1") (pin "P$89") (pinfunction "VSS_PAD_P$89") (pintype "bidirectional"))
      (node (ref "U1") (pin "P$90") (pinfunction "VSS_PAD_P$90") (pintype "bidirectional"))
      (node (ref "U1") (pin "P$F23") (pinfunction "VSS_PA_P$F23") (pintype "bidirectional"))
      (node (ref "U3") (pin "1") (pinfunction "CTG_1") (pintype "power_in"))
      (node (ref "U3") (pin "4") (pinfunction "GND_4") (pintype "power_in"))
      (node (ref "U3") (pin "6") (pinfunction "QSTRT_6") (pintype "input"))
      (node (ref "U3") (pin "9") (pinfunction "EP_9") (pintype "power_in"))
      (node (ref "X1") (pin "2") (pinfunction "2_2") (pintype "passive"))
      (node (ref "X1") (pin "4") (pinfunction "4_4") (pintype "passive"))
    )
    (net (code "14") (name "HAPTIC_EN") (class "Default")
      (node (ref "IC2") (pin "A1") (pinfunction "EN_A1") (pintype "bidirectional"))
      (node (ref "U1") (pin "P$U1") (pinfunction "P0.12_P$U1") (pintype "bidirectional"))
    )
    (net (code "15") (name "IMU_INT1") (class "Default")
      (node (ref "IC3") (pin "5") (pinfunction "INT1_5") (pintype "bidirectional"))
      (node (ref "U1") (pin "P$N1") (pinfunction "P0.08_P$N1") (pintype "bidirectional"))
    )
    (net (code "16") (name "IMU_INT2") (class "Default")
      (node (ref "IC3") (pin "6") (pinfunction "INT2_6") (pintype "bidirectional"))
      (node (ref "U1") (pin "P$P2") (pinfunction "P1.08_P$P2") (pintype "bidirectional"))
    )
    (net (code "17") (name "LX1") (class "Default")
      (node (ref "IC9") (pin "B2") (pinfunction "SW1_1_B2") (pintype "bidirectional"))
      (node (ref "IC9") (pin "B3") (pinfunction "SW1_2_B3") (pintype "bidirectional"))
      (node (ref "L7") (pin "1") (pinfunction "1_1") (pintype "bidirectional"))
    )
    (net (code "18") (name "LX2") (class "Default")
      (node (ref "IC9") (pin "D2") (pinfunction "SW2_1_D2") (pintype "bidirectional"))
      (node (ref "IC9") (pin "D3") (pinfunction "SW2_2_D3") (pintype "bidirectional"))
      (node (ref "L7") (pin "2") (pinfunction "2_2") (pintype "bidirectional"))
    )
    (net (code "19") (name "MOSI") (class "Default")
      (node (ref "J1") (pin "14") (pinfunction "14_14") (pintype "bidirectional"))
      (node (ref "U1") (pin "P$B13") (pinfunction "P0.03/AIN1_P$B13") (pintype "bidirectional"))
    )
    (net (code "20") (name "Net-(ANT1-FEED)") (class "Default")
      (node (ref "ANT1") (pin "1") (pinfunction "FEED_1") (pintype "input"))
      (node (ref "C22") (pin "2") (pinfunction "2_2") (pintype "passive"))
      (node (ref "C4") (pin "2") (pinfunction "2_2") (pintype "passive"))
      (node (ref "L1") (pin "2") (pinfunction "2_2") (pintype "passive"))
    )
    (net (code "21") (name "Net-(D2-K)") (class "Default")
      (node (ref "C2-EP-DR") (pin "1") (pinfunction "1_1") (pintype "passive"))
      (node (ref "D2") (pin "1") (pinfunction "K_1") (pintype "bidirectional"))
      (node (ref "D4") (pin "2") (pinfunction "A_2") (pintype "bidirectional"))
    )
    (net (code "22") (name "Net-(D5-A)") (class "Default")
      (node (ref "C2-EP-DR") (pin "2") (pinfunction "2_2") (pintype "passive"))
      (node (ref "D5") (pin "2") (pinfunction "A_2") (pintype "bidirectional"))
      (node (ref "L5") (pin "1") (pinfunction "1_1") (pintype "passive"))
      (node (ref "Q3") (pin "3") (pinfunction "D_3") (pintype "bidirectional"))
    )
    (net (code "23") (name "Net-(EPD_C1-Pad2)") (class "Default")
      (node (ref "EPD_C1") (pin "2") (pinfunction "2_2") (pintype "passive"))
      (node (ref "J1") (pin "5") (pinfunction "5_5") (pintype "bidirectional"))
    )
    (net (code "24") (name "Net-(EPD_C2-Pad2)") (class "Default")
      (node (ref "EPD_C2") (pin "2") (pinfunction "2_2") (pintype "passive"))
      (node (ref "J1") (pin "4") (pinfunction "4_4") (pintype "bidirectional"))
    )
    (net (code "25") (name "Net-(EPD_C6-Pad2)") (class "Default")
      (node (ref "EPD_C6") (pin "2") (pinfunction "2_2") (pintype "passive"))
      (node (ref "J1") (pin "18") (pinfunction "18_18") (pintype "bidirectional"))
    )
    (net (code "26") (name "Net-(EPD_C7-Pad2)") (class "Default")
      (node (ref "EPD_C7") (pin "2") (pinfunction "2_2") (pintype "passive"))
      (node (ref "J1") (pin "19") (pinfunction "19_19") (pintype "bidirectional"))
    )
    (net (code "27") (name "Net-(EPD_C8-Pad2)") (class "Default")
      (node (ref "EPD_C8") (pin "2") (pinfunction "2_2") (pintype "passive"))
      (node (ref "J1") (pin "20") (pinfunction "20_20") (pintype "bidirectional"))
    )
    (net (code "28") (name "Net-(EPD_C10-Pad2)") (class "Default")
      (node (ref "EPD_C10") (pin "2") (pinfunction "2_2") (pintype "passive"))
      (node (ref "J1") (pin "22") (pinfunction "22_22") (pintype "bidirectional"))
    )
    (net (code "29") (name "Net-(EPD_C12-Pad2)") (class "Default")
      (node (ref "EPD_C12") (pin "2") (pinfunction "2_2") (pintype "passive"))
      (node (ref "J1") (pin "24") (pinfunction "24_24") (pintype "bidirectional"))
    )
    (net (code "30") (name "Net-(IC1-TS{slash}MR)") (class "Default")
      (node (ref "IC1") (pin "D1") (pinfunction "TS/MR_D1") (pintype "bidirectional"))
      (node (ref "R9") (pin "1") (pinfunction "1_1") (pintype "bidirectional"))
    )
    (net (code "31") (name "Net-(IC2-REG)") (class "Default")
      (node (ref "C32") (pin "1") (pinfunction "1_1") (pintype "passive"))
      (node (ref "IC2") (pin "A2") (pinfunction "REG_A2") (pintype "bidirectional"))
    )
    (net (code "32") (name "Net-(IC3-SDO)") (class "Default")
      (node (ref "IC3") (pin "1") (pinfunction "SDO_1") (pintype "bidirectional"))
      (node (ref "R3") (pin "1") (pinfunction "1_1") (pintype "bidirectional"))
    )
    (net (code "33") (name "Net-(IC9-SCL)") (class "Default")
      (node (ref "IC9") (pin "D1") (pinfunction "SCL_D1") (pintype "bidirectional"))
      (node (ref "R4") (pin "1") (pinfunction "1_1") (pintype "bidirectional"))
    )
    (net (code "34") (name "Net-(IC9-SDA)") (class "Default")
      (node (ref "IC9") (pin "E1") (pinfunction "SDA_E1") (pintype "bidirectional"))
      (node (ref "R2") (pin "1") (pinfunction "1_1") (pintype "bidirectional"))
    )
    (net (code "35") (name "Net-(J4-CC1)") (class "Default")
      (node (ref "J4") (pin "A5") (pinfunction "CC1_A5") (pintype "bidirectional"))
      (node (ref "R1_USB") (pin "2") (pinfunction "2_2") (pintype "bidirectional"))
    )
    (net (code "36") (name "Net-(J4-CC2)") (class "Default")
      (node (ref "J4") (pin "B5") (pinfunction "CC2_B5") (pintype "bidirectional"))
      (node (ref "R2_USB") (pin "1") (pinfunction "1_1") (pintype "bidirectional"))
    )
    (net (code "37") (name "Net-(L2-Pad2)") (class "Default")
      (node (ref "L2") (pin "2") (pinfunction "2_2") (pintype "passive"))
      (node (ref "L3") (pin "1") (pinfunction "1_1") (pintype "passive"))
    )
    (net (code "38") (name "Net-(R1_EP_DR-Pad1)") (class "Default")
      (node (ref "R1_EP_DR") (pin "1") (pinfunction "1_1") (pintype "bidirectional"))
      (node (ref "R_TYPE_SEL") (pin "2") (pinfunction "2_2") (pintype "bidirectional"))
      (node (ref "SJ1") (pin "2") (pinfunction "2_2") (pintype "passive"))
    )
    (net (code "39") (name "Net-(U1-ANT)") (class "Default")
      (node (ref "C3") (pin "2") (pinfunction "2_2") (pintype "passive"))
      (node (ref "L1") (pin "1") (pinfunction "1_1") (pintype "passive"))
      (node (ref "U1") (pin "P$H23") (pinfunction "ANT_P$H23") (pintype "bidirectional"))
    )
    (net (code "40") (name "Net-(U1-DCC)") (class "Default")
      (node (ref "L2") (pin "1") (pinfunction "1_1") (pintype "passive"))
      (node (ref "U1") (pin "P$B3") (pinfunction "DCC_P$B3") (pintype "output"))
    )
    (net (code "41") (name "Net-(U1-DEC1)") (class "Default")
      (node (ref "C5") (pin "2") (pinfunction "2_2") (pintype "passive"))
      (node (ref "U1") (pin "P$C1") (pinfunction "DEC1_P$C1") (pintype "power_in"))
    )
    (net (code "42") (name "Net-(U1-DEC2)") (class "Default")
      (node (ref "C13") (pin "2") (pinfunction "2_2") (pintype "passive"))
      (node (ref "U1") (pin "P$A18") (pinfunction "DEC2_P$A18") (pintype "bidirectional"))
    )
    (net (code "43") (name "Net-(U1-DEC3)") (class "Default")
      (node (ref "C11") (pin "2") (pinfunction "2_2") (pintype "passive"))
      (node (ref "U1") (pin "P$D23") (pinfunction "DEC3_P$D23") (pintype "bidirectional"))
    )
    (net (code "44") (name "Net-(U1-DEC3V3)") (class "Default")
      (node (ref "C20") (pin "1") (pinfunction "1_1") (pintype "passive"))
      (node (ref "U1") (pin "P$AC5") (pinfunction "DEC3V3_P$AC5") (pintype "bidirectional"))
    )
    (net (code "45") (name "Net-(U1-DEC4)") (class "Default")
      (node (ref "C10") (pin "2") (pinfunction "2_2") (pintype "passive"))
      (node (ref "C15") (pin "1") (pinfunction "1_1") (pintype "passive"))
      (node (ref "C16") (pin "2") (pinfunction "2_2") (pintype "passive"))
      (node (ref "L3") (pin "2") (pinfunction "2_2") (pintype "passive"))
      (node (ref "U1") (pin "P$B5") (pinfunction "DEC4_P$B5") (pintype "power_in"))
      (node (ref "U1") (pin "P$E24") (pinfunction "DEC6_P$E24") (pintype "bidirectional"))
    )
    (net (code "46") (name "Net-(U1-DEC5)") (class "Default")
      (node (ref "C9") (pin "2") (pinfunction "2_2") (pintype "passive"))
      (node (ref "U1") (pin "P$N24") (pinfunction "DEC5_P$N24") (pintype "bidirectional"))
    )
    (net (code "47") (name "Net-(U1-P0.00{slash}XL1)") (class "Default")
      (node (ref "C17") (pin "2") (pinfunction "2_2") (pintype "passive"))
      (node (ref "U1") (pin "P$D2") (pinfunction "P0.00/XL1_P$D2") (pintype "bidirectional"))
      (node (ref "X2") (pin "2") (pinfunction "2_2") (pintype "passive"))
    )
    (net (code "48") (name "Net-(U1-P0.01{slash}XL2)") (class "Default")
      (node (ref "C18") (pin "2") (pinfunction "2_2") (pintype "passive"))
      (node (ref "U1") (pin "P$F2") (pinfunction "P0.01/XL2_P$F2") (pintype "bidirectional"))
      (node (ref "X2") (pin "1") (pinfunction "1_1") (pintype "passive"))
    )
    (net (code "49") (name "Net-(U1-VSS)") (class "Default")
      (node (ref "C15") (pin "2") (pinfunction "2_2") (pintype "passive"))
      (node (ref "C16") (pin "1") (pinfunction "1_1") (pintype "passive"))
      (node (ref "U1") (pin "P$B7") (pinfunction "VSS_P$B7") (pintype "power_in"))
    )
    (net (code "50") (name "Net-(U1-XC1)") (class "Default")
      (node (ref "C1") (pin "1") (pinfunction "1_1") (pintype "passive"))
      (node (ref "U1") (pin "P$B24") (pinfunction "XC1_P$B24") (pintype "input"))
      (node (ref "X1") (pin "1") (pinfunction "1_1") (pintype "passive"))
    )
    (net (code "51") (name "Net-(U1-XC2)") (class "Default")
      (node (ref "C2") (pin "1") (pinfunction "1_1") (pintype "passive"))
      (node (ref "U1") (pin "P$A23") (pinfunction "XC2_P$A23") (pintype "output"))
      (node (ref "X1") (pin "3") (pinfunction "3_3") (pintype "passive"))
    )
    (net (code "52") (name "OUT+") (class "Default")
      (node (ref "IC2") (pin "A3") (pinfunction "OUT+_A3") (pintype "bidirectional"))
      (node (ref "TP_ON") (pin "TP") (pinfunction "TP_TP") (pintype "input"))
    )
    (net (code "53") (name "OUT-") (class "Default")
      (node (ref "IC2") (pin "C3") (pinfunction "OUT-_C3") (pintype "bidirectional"))
      (node (ref "TP_OP") (pin "TP") (pinfunction "TP_TP") (pintype "input"))
    )
    (net (code "54") (name "P0.04") (class "Default")
      (node (ref "U1") (pin "P$J1") (pinfunction "P0.04/AIN2_P$J1") (pintype "bidirectional"))
    )
    (net (code "55") (name "P0.09") (class "Default")
      (node (ref "U1") (pin "P$L24") (pinfunction "P0.09/NFC1_P$L24") (pintype "bidirectional"))
    )
    (net (code "56") (name "P0.13") (class "Default")
      (node (ref "C30") (pin "1") (pinfunction "1_1") (pintype "passive"))
      (node (ref "R5") (pin "1") (pinfunction "1_1") (pintype "bidirectional"))
      (node (ref "SW_UP") (pin "2") (pinfunction "2_2") (pintype "passive"))
      (node (ref "U1") (pin "P$AD8") (pinfunction "P0.13_P$AD8") (pintype "bidirectional"))
    )
    (net (code "57") (name "P0.14") (class "Default")
      (node (ref "C31") (pin "1") (pinfunction "1_1") (pintype "passive"))
      (node (ref "R8") (pin "1") (pinfunction "1_1") (pintype "bidirectional"))
      (node (ref "SW_ENT") (pin "2") (pinfunction "2_2") (pintype "passive"))
      (node (ref "U1") (pin "P$AC9") (pinfunction "P0.14_P$AC9") (pintype "bidirectional"))
    )
    (net (code "58") (name "P0.19") (class "Default")
      (node (ref "U1") (pin "P$AC15") (pinfunction "P0.19_P$AC15") (pintype "bidirectional"))
    )
    (net (code "59") (name "P0.20") (class "Default")
      (node (ref "U1") (pin "P$AD16") (pinfunction "P0.20_P$AD16") (pintype "bidirectional"))
    )
    (net (code "60") (name "P0.21") (class "Default")
      (node (ref "U1") (pin "P$AC17") (pinfunction "P0.21_P$AC17") (pintype "bidirectional"))
    )
    (net (code "61") (name "P0.22") (class "Default")
      (node (ref "U1") (pin "P$AD18") (pinfunction "P0.22_P$AD18") (pintype "bidirectional"))
    )
    (net (code "62") (name "P0.23") (class "Default")
      (node (ref "U1") (pin "P$AC19") (pinfunction "P0.23_P$AC19") (pintype "bidirectional"))
    )
    (net (code "63") (name "P0.24") (class "Default")
      (node (ref "U1") (pin "P$AD20") (pinfunction "P0.24_P$AD20") (pintype "bidirectional"))
    )
    (net (code "64") (name "P0.25") (class "Default")
      (node (ref "U1") (pin "P$AC21") (pinfunction "P0.25_P$AC21") (pintype "bidirectional"))
    )
    (net (code "65") (name "P0.26") (class "Default")
      (node (ref "U1") (pin "P$G1") (pinfunction "P0.26_P$G1") (pintype "bidirectional"))
    )
    (net (code "66") (name "P0.27") (class "Default")
      (node (ref "U1") (pin "P$H2") (pinfunction "P0.27_P$H2") (pintype "bidirectional"))
    )
    (net (code "67") (name "P0.28") (class "Default")
      (node (ref "U1") (pin "P$B11") (pinfunction "P0.28/AIN4_P$B11") (pintype "bidirectional"))
    )
    (net (code "68") (name "P0.29") (class "Default")
      (node (ref "U1") (pin "P$A10") (pinfunction "P0.29/AIN5_P$A10") (pintype "bidirectional"))
    )
    (net (code "69") (name "P0.30") (class "Default")
      (node (ref "U1") (pin "P$B9") (pinfunction "P0.30/AIN6_P$B9") (pintype "bidirectional"))
    )
    (net (code "70") (name "P0.31") (class "Default")
      (node (ref "U1") (pin "P$A8") (pinfunction "P0.31/AIN7_P$A8") (pintype "bidirectional"))
    )
    (net (code "71") (name "P1.01") (class "Default")
      (node (ref "Q1") (pin "1") (pinfunction "G_1") (pintype "bidirectional"))
      (node (ref "R_PWR_EPD") (pin "1") (pinfunction "1_1") (pintype "bidirectional"))
      (node (ref "U1") (pin "P$Y23") (pinfunction "P1.01_P$Y23") (pintype "bidirectional"))
    )
    (net (code "72") (name "P1.02") (class "Default")
      (node (ref "C29") (pin "1") (pinfunction "1_1") (pintype "passive"))
      (node (ref "R7") (pin "1") (pinfunction "1_1") (pintype "bidirectional"))
      (node (ref "SW_DN") (pin "2") (pinfunction "2_2") (pintype "passive"))
      (node (ref "U1") (pin "P$W24") (pinfunction "P1.02_P$W24") (pintype "bidirectional"))
    )
    (net (code "73") (name "P1.03") (class "Default")
      (node (ref "U1") (pin "P$V23") (pinfunction "P1.03_P$V23") (pintype "bidirectional"))
    )
    (net (code "74") (name "P1.04") (class "Default")
      (node (ref "U1") (pin "P$U24") (pinfunction "P1.04_P$U24") (pintype "bidirectional"))
    )
    (net (code "75") (name "P1.05") (class "Default")
      (node (ref "U1") (pin "P$T23") (pinfunction "P1.05_P$T23") (pintype "bidirectional"))
    )
    (net (code "76") (name "P1.06") (class "Default")
      (node (ref "U1") (pin "P$R24") (pinfunction "P1.06_P$R24") (pintype "bidirectional"))
    )
    (net (code "77") (name "P1.07") (class "Default")
      (node (ref "U1") (pin "P$P23") (pinfunction "P1.07_P$P23") (pintype "bidirectional"))
    )
    (net (code "78") (name "P1.09") (class "Default")
      (node (ref "U1") (pin "P$R1") (pinfunction "P1.09_P$R1") (pintype "bidirectional"))
    )
    (net (code "79") (name "P1.10") (class "Default")
      (node (ref "U1") (pin "P$A20") (pinfunction "P1.10_P$A20") (pintype "bidirectional"))
    )
    (net (code "80") (name "P1.11") (class "Default")
      (node (ref "U1") (pin "P$B19") (pinfunction "P1.11_P$B19") (pintype "bidirectional"))
    )
    (net (code "81") (name "P1.12") (class "Default")
      (node (ref "U1") (pin "P$B17") (pinfunction "P1.12_P$B17") (pintype "bidirectional"))
    )
    (net (code "82") (name "P1.13") (class "Default")
      (node (ref "U1") (pin "P$A16") (pinfunction "P1.13_P$A16") (pintype "bidirectional"))
    )
    (net (code "83") (name "P1.14") (class "Default")
      (node (ref "U1") (pin "P$B15") (pinfunction "P1.14_P$B15") (pintype "bidirectional"))
    )
    (net (code "84") (name "P1.15") (class "Default")
      (node (ref "U1") (pin "P$A14") (pinfunction "P1.15_P$A14") (pintype "bidirectional"))
    )
    (net (code "85") (name "PMIC_INT") (class "Default")
      (node (ref "IC1") (pin "A1") (pinfunction "~{INT}_A1") (pintype "bidirectional"))
      (node (ref "U1") (pin "P$T2") (pinfunction "P0.11_P$T2") (pintype "bidirectional"))
    )
    (net (code "86") (name "PREPGH") (class "Default")
      (node (ref "D5") (pin "1") (pinfunction "K_1") (pintype "bidirectional"))
      (node (ref "EPD_C9") (pin "2") (pinfunction "2_2") (pintype "passive"))
      (node (ref "J1") (pin "21") (pinfunction "21_21") (pintype "bidirectional"))
    )
    (net (code "87") (name "PREVGL") (class "Default")
      (node (ref "D2") (pin "2") (pinfunction "A_2") (pintype "bidirectional"))
      (node (ref "EPD_C11") (pin "2") (pinfunction "2_2") (pintype "passive"))
      (node (ref "J1") (pin "23") (pinfunction "23_23") (pintype "bidirectional"))
    )
    (net (code "88") (name "RESE") (class "Default")
      (node (ref "J1") (pin "3") (pinfunction "3_3") (pintype "bidirectional"))
      (node (ref "Q3") (pin "2") (pinfunction "S_2") (pintype "bidirectional"))
      (node (ref "R1_EP_DR") (pin "2") (pinfunction "2_2") (pintype "bidirectional"))
    )
    (net (code "89") (name "RESET") (class "Default")
      (node (ref "J2") (pin "6") (pinfunction "6_6") (pintype "bidirectional"))
      (node (ref "TP_RESET") (pin "TP") (pinfunction "TP_TP") (pintype "input"))
      (node (ref "U1") (pin "P$AC13") (pinfunction "P0.18/RESET_P$AC13") (pintype "bidirectional"))
    )
    (net (code "90") (name "SCK") (class "Default")
      (node (ref "J1") (pin "13") (pinfunction "13_13") (pintype "bidirectional"))
      (node (ref "U1") (pin "P$A12") (pinfunction "P0.02/AIN0_P$A12") (pintype "bidirectional"))
    )
    (net (code "91") (name "SCL") (class "Default")
      (node (ref "IC1") (pin "B1") (pinfunction "SCL_B1") (pintype "bidirectional"))
      (node (ref "IC2") (pin "C1") (pinfunction "SCL_C1") (pintype "bidirectional"))
      (node (ref "IC3") (pin "12") (pinfunction "SCX_12") (pintype "bidirectional"))
      (node (ref "R17") (pin "2") (pinfunction "2_2") (pintype "bidirectional"))
      (node (ref "R4") (pin "2") (pinfunction "2_2") (pintype "bidirectional"))
      (node (ref "TP_SCL") (pin "TP") (pinfunction "TP_TP") (pintype "input"))
      (node (ref "U1") (pin "P$M2") (pinfunction "P0.07_P$M2") (pintype "bidirectional"))
      (node (ref "U3") (pin "7") (pinfunction "SCL_7") (pintype "input"))
    )
    (net (code "92") (name "SDA") (class "Default")
      (node (ref "IC1") (pin "C1") (pinfunction "SDA_C1") (pintype "bidirectional"))
      (node (ref "IC2") (pin "B2") (pinfunction "SDA_B2") (pintype "bidirectional"))
      (node (ref "IC3") (pin "2") (pinfunction "SDX_2") (pintype "bidirectional"))
      (node (ref "R18") (pin "2") (pinfunction "2_2") (pintype "bidirectional"))
      (node (ref "R2") (pin "2") (pinfunction "2_2") (pintype "bidirectional"))
      (node (ref "TP_SDA") (pin "TP") (pinfunction "TP_TP") (pintype "input"))
      (node (ref "U1") (pin "P$L1") (pinfunction "P0.06_P$L1") (pintype "bidirectional"))
      (node (ref "U3") (pin "8") (pinfunction "SDA_8") (pintype "bidirectional"))
    )
    (net (code "93") (name "SWDCLK") (class "Default")
      (node (ref "J2") (pin "4") (pinfunction "4_4") (pintype "bidirectional"))
      (node (ref "TP_SWDCLK") (pin "TP") (pinfunction "TP_TP") (pintype "input"))
      (node (ref "U1") (pin "P$AA24") (pinfunction "SWDCLK_P$AA24") (pintype "input"))
    )
    (net (code "94") (name "SWDIO") (class "Default")
      (node (ref "J2") (pin "2") (pinfunction "2_2") (pintype "bidirectional"))
      (node (ref "TP_SWDIO") (pin "TP") (pinfunction "TP_TP") (pintype "input"))
      (node (ref "U1") (pin "P$AC24") (pinfunction "SWDIO_P$AC24") (pintype "bidirectional"))
    )
    (net (code "95") (name "SWO") (class "Default")
      (node (ref "TP_SWO") (pin "TP") (pinfunction "TP_TP") (pintype "input"))
      (node (ref "U1") (pin "P$AD22") (pinfunction "P1.00_P$AD22") (pintype "bidirectional"))
    )
    (net (code "96") (name "VBAT") (class "Default")
      (node (ref "C27") (pin "2") (pinfunction "2_2") (pintype "passive"))
      (node (ref "C37") (pin "1") (pinfunction "1_1") (pintype "passive"))
      (node (ref "IC1") (pin "C2") (pinfunction "BAT_C2") (pintype "bidirectional"))
      (node (ref "TP_VBAT") (pin "TP") (pinfunction "TP_TP") (pintype "input"))
      (node (ref "U3") (pin "2") (pinfunction "CELL_2") (pintype "power_in"))
      (node (ref "U3") (pin "3") (pinfunction "VDD_3") (pintype "power_in"))
    )
    (net (code "97") (name "VBUS") (class "Default")
      (node (ref "C21") (pin "1") (pinfunction "1_1") (pintype "passive"))
      (node (ref "C38") (pin "1") (pinfunction "1_1") (pintype "passive"))
      (node (ref "C42") (pin "2") (pinfunction "2_2") (pintype "passive"))
      (node (ref "C43") (pin "1") (pinfunction "1_1") (pintype "passive"))
      (node (ref "D3") (pin "5") (pinfunction "VBUS_5") (pintype "bidirectional"))
      (node (ref "IC1") (pin "A2") (pinfunction "IN_A2") (pintype "bidirectional"))
      (node (ref "J4") (pin "A4_B9") (pinfunction "VBUS_A4_B9") (pintype "power_in"))
      (node (ref "J4") (pin "A9_B4") (pinfunction "VBUS_A9_B4") (pintype "power_in"))
      (node (ref "U1") (pin "P$AD2") (pinfunction "VBUS_P$AD2") (pintype "power_in"))
    )
    (net (code "98") (name "VREG") (class "Default")
      (node (ref "C23") (pin "1") (pinfunction "1_1") (pintype "passive"))
      (node (ref "C24") (pin "2") (pinfunction "2_2") (pintype "passive"))
      (node (ref "C39") (pin "1") (pinfunction "1_1") (pintype "passive"))
      (node (ref "IC1") (pin "B2") (pinfunction "SYS_B2") (pintype "bidirectional"))
      (node (ref "IC9") (pin "A1") (pinfunction "EN_A1") (pintype "bidirectional"))
      (node (ref "IC9") (pin "A2") (pinfunction "VIN_1_A2") (pintype "bidirectional"))
      (node (ref "IC9") (pin "A3") (pinfunction "VIN_2_A3") (pintype "bidirectional"))
      (node (ref "TP_VREG") (pin "TP") (pinfunction "TP_TP") (pintype "input"))
    )
    (net (code "99") (name "unconnected-(ANT1-NC-Pad2)") (class "Default")
      (node (ref "ANT1") (pin "2") (pinfunction "NC_2") (pintype "no_connect"))
    )
    (net (code "100") (name "unconnected-(IC3-ASCL-Pad11)") (class "Default")
      (node (ref "IC3") (pin "11") (pinfunction "ASCL_11") (pintype "bidirectional"))
    )
    (net (code "101") (name "unconnected-(IC3-ASDA-Pad4)") (class "Default")
      (node (ref "IC3") (pin "4") (pinfunction "ASDA_4") (pintype "bidirectional"))
    )
    (net (code "102") (name "unconnected-(J1-Pad1)") (class "Default")
      (node (ref "J1") (pin "1") (pinfunction "1_1") (pintype "bidirectional"))
    )
    (net (code "103") (name "unconnected-(J1-Pad6)") (class "Default")
      (node (ref "J1") (pin "6") (pinfunction "6_6") (pintype "bidirectional"))
    )
    (net (code "104") (name "unconnected-(J1-Pad7)") (class "Default")
      (node (ref "J1") (pin "7") (pinfunction "7_7") (pintype "bidirectional"))
    )
    (net (code "105") (name "unconnected-(J4-SBU1-PadA8)") (class "Default")
      (node (ref "J4") (pin "A8") (pinfunction "SBU1_A8") (pintype "bidirectional"))
    )
    (net (code "106") (name "unconnected-(J4-SBU2-PadB8)") (class "Default")
      (node (ref "J4") (pin "B8") (pinfunction "SBU2_B8") (pintype "bidirectional"))
    )
    (net (code "107") (name "unconnected-(U1-DCCH-PadP$AB2)") (class "Default")
      (node (ref "U1") (pin "P$AB2") (pinfunction "DCCH_P$AB2") (pintype "bidirectional"))
    )
  )
)
